# Sheet1.net
KiCad netlist of a schematic drawn in Altium Designer
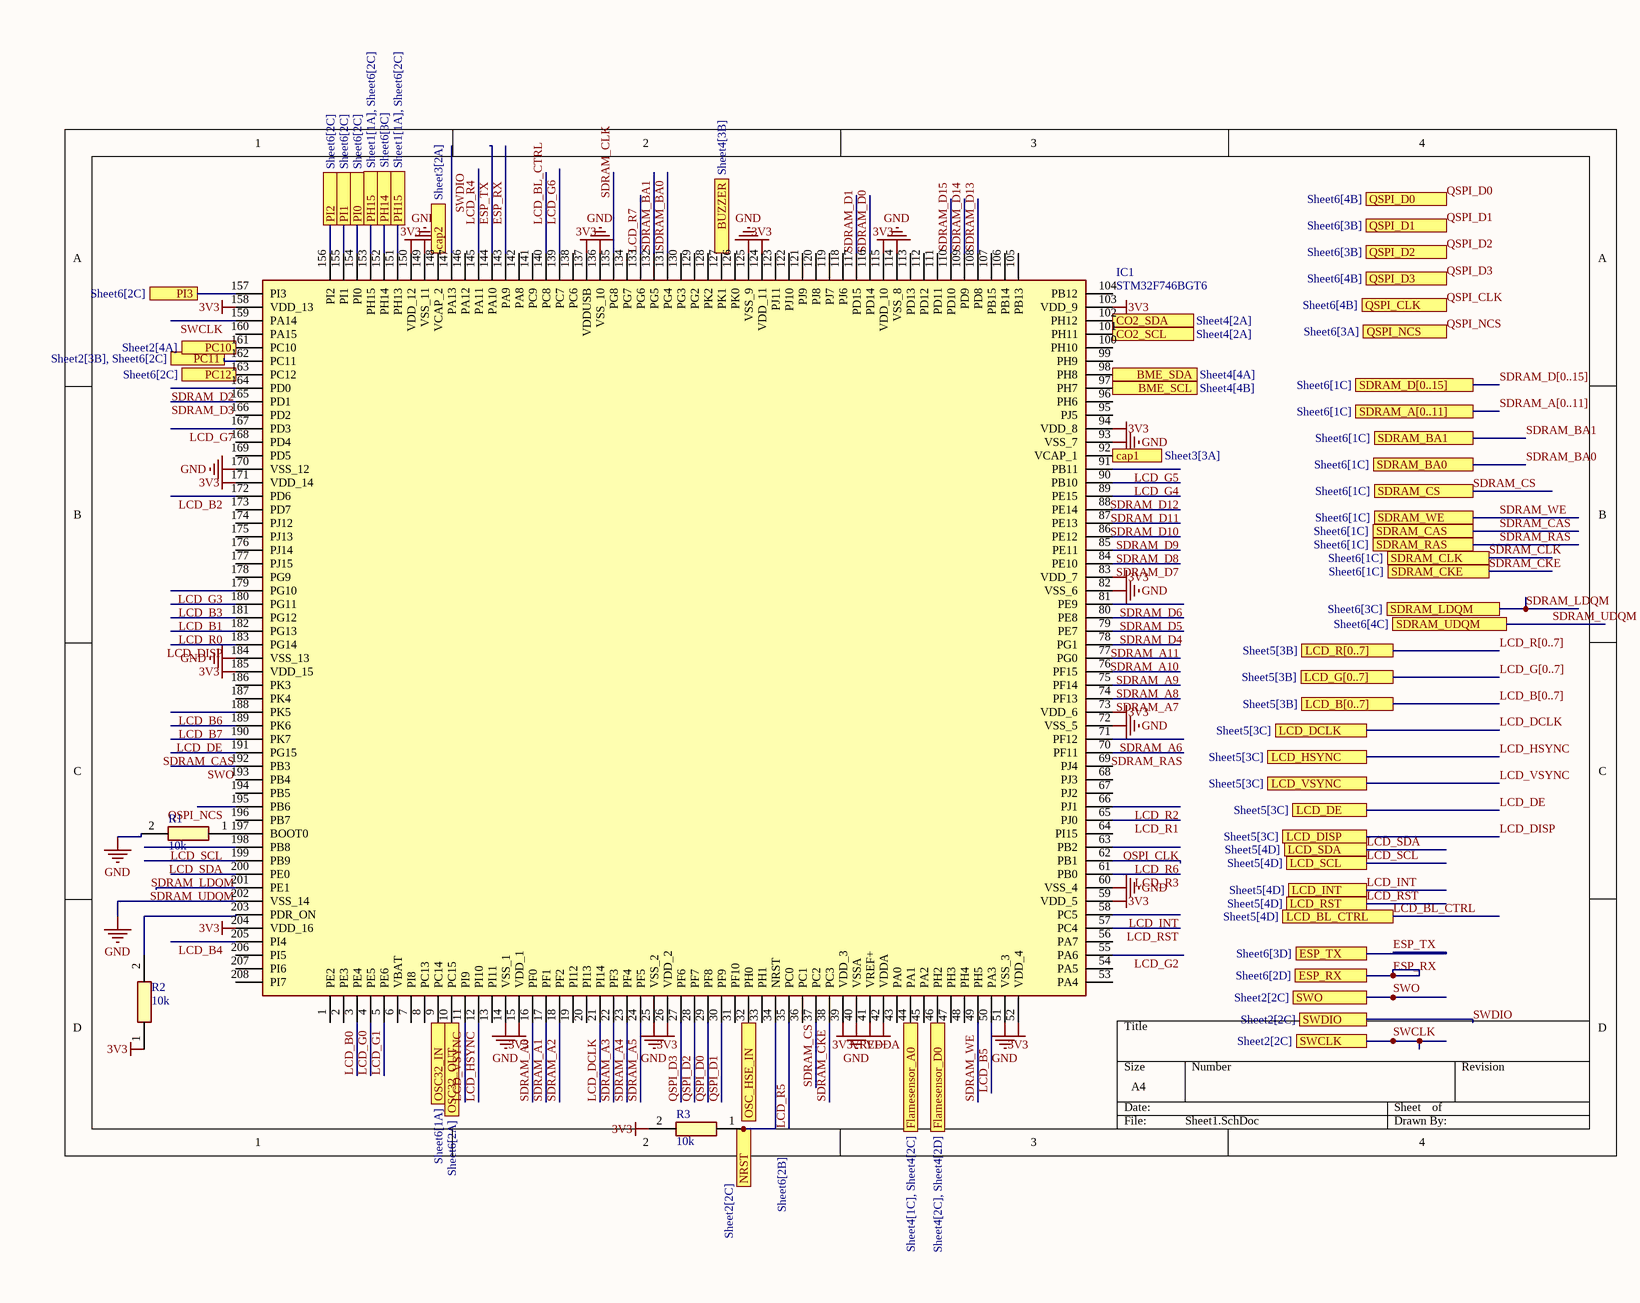
[diagram p0: Sheet1.SchDoc]

(export (version "E")
  (design (tool "Eeschema 10.0.6"))
  (components
    (comp (ref "IC1")
      (value "STM32F746BGT6")
      (footprint "SamacSys:QFP50P3000X3000X160-208N")
      (description "Integrated Circuit")
      (fields (field (name "MOUSER PART NUMBER") "511-STM32F746BGT6"))
      (libsource (lib "SamacSys") (part "STM32F746BGT6"))
    )
    (comp (ref "R1")
      (value "10k")
      (footprint "SamacSys:RESC1608X55N")
      (description "Resistor")
      (fields
        (field (name "MANUFACTURER_PART_NUMBER") "RC0603FR-071KL")
        (field (name "MOUSER PART NUMBER") "603-RC0603FR-071KL")
      )
      (libsource (lib "*") (part "RC0603FR-071KL"))
    )
    (comp (ref "R2")
      (value "10k")
      (footprint "SamacSys:RESC1608X55N")
      (description "Resistor")
      (fields
        (field (name "MANUFACTURER_PART_NUMBER") "RC0603FR-071KL")
        (field (name "MOUSER PART NUMBER") "603-RC0603FR-071KL")
      )
      (libsource (lib "") (part "RC0603FR-071KL_1"))
    )
    (comp (ref "R3")
      (value "10k")
      (footprint "SamacSys:RESC1608X55N")
      (description "Resistor")
      (fields
        (field (name "MANUFACTURER_PART_NUMBER") "RC0603FR-071KL")
        (field (name "MOUSER PART NUMBER") "603-RC0603FR-071KL")
      )
      (libsource (lib "*") (part "RC0603FR-071KL"))
    )
  )
  (nets
    (net (code "1") (name "/BME_SCL") (class "Default")
      (node (ref "IC1") (pin "97") (pinfunction "PH7_97") (pintype "passive"))
    )
    (net (code "2") (name "/BME_SDA") (class "Default")
      (node (ref "IC1") (pin "98") (pinfunction "PH8_98") (pintype "passive"))
    )
    (net (code "3") (name "/BUZZER") (class "Default")
      (node (ref "IC1") (pin "127") (pinfunction "PK1_127") (pintype "passive"))
    )
    (net (code "4") (name "/CO2_SCL") (class "Default")
      (node (ref "IC1") (pin "101") (pinfunction "PH11_101") (pintype "passive"))
    )
    (net (code "5") (name "/CO2_SDA") (class "Default")
      (node (ref "IC1") (pin "102") (pinfunction "PH12_102") (pintype "passive"))
    )
    (net (code "6") (name "/ESP_RX") (class "Default")
      (node (ref "IC1") (pin "143") (pinfunction "PA9_143") (pintype "passive"))
    )
    (net (code "7") (name "/ESP_TX") (class "Default")
      (node (ref "IC1") (pin "144") (pinfunction "PA10_144") (pintype "passive"))
    )
    (net (code "8") (name "/Flamesensor_A0") (class "Default")
      (node (ref "IC1") (pin "44") (pinfunction "PA1_44") (pintype "passive"))
    )
    (net (code "9") (name "/Flamesensor_D0") (class "Default")
      (node (ref "IC1") (pin "46") (pinfunction "PH2_46") (pintype "passive"))
    )
    (net (code "10") (name "/LCD_B0") (class "Default")
      (node (ref "IC1") (pin "3") (pinfunction "PE4_3") (pintype "passive"))
    )
    (net (code "11") (name "/LCD_B1") (class "Default")
      (node (ref "IC1") (pin "181") (pinfunction "PG12_181") (pintype "passive"))
    )
    (net (code "12") (name "/LCD_B2") (class "Default")
      (node (ref "IC1") (pin "172") (pinfunction "PD6_172") (pintype "passive"))
    )
    (net (code "13") (name "/LCD_B3") (class "Default")
      (node (ref "IC1") (pin "180") (pinfunction "PG11_180") (pintype "passive"))
    )
    (net (code "14") (name "/LCD_B4") (class "Default")
      (node (ref "IC1") (pin "205") (pinfunction "PI4_205") (pintype "passive"))
    )
    (net (code "15") (name "/LCD_B5") (class "Default")
      (node (ref "IC1") (pin "50") (pinfunction "PA3_50") (pintype "passive"))
    )
    (net (code "16") (name "/LCD_B6") (class "Default")
      (node (ref "IC1") (pin "188") (pinfunction "PK5_188") (pintype "passive"))
    )
    (net (code "17") (name "/LCD_B7") (class "Default")
      (node (ref "IC1") (pin "189") (pinfunction "PK6_189") (pintype "passive"))
    )
    (net (code "18") (name "/LCD_BL_CTRL") (class "Default")
      (node (ref "IC1") (pin "140") (pinfunction "PC8_140") (pintype "passive"))
    )
    (net (code "20") (name "/LCD_DCLK") (class "Default")
      (node (ref "IC1") (pin "21") (pinfunction "PI14_21") (pintype "passive"))
    )
    (net (code "21") (name "/LCD_DE") (class "Default")
      (node (ref "IC1") (pin "190") (pinfunction "PK7_190") (pintype "passive"))
    )
    (net (code "22") (name "/LCD_DISP") (class "Default")
      (node (ref "IC1") (pin "183") (pinfunction "PG14_183") (pintype "passive"))
    )
    (net (code "23") (name "/LCD_G0") (class "Default")
      (node (ref "IC1") (pin "4") (pinfunction "PE5_4") (pintype "passive"))
    )
    (net (code "24") (name "/LCD_G1") (class "Default")
      (node (ref "IC1") (pin "5") (pinfunction "PE6_5") (pintype "passive"))
    )
    (net (code "25") (name "/LCD_G2") (class "Default")
      (node (ref "IC1") (pin "55") (pinfunction "PA6_55") (pintype "passive"))
    )
    (net (code "26") (name "/LCD_G3") (class "Default")
      (node (ref "IC1") (pin "179") (pinfunction "PG10_179") (pintype "passive"))
    )
    (net (code "27") (name "/LCD_G4") (class "Default")
      (node (ref "IC1") (pin "90") (pinfunction "PB10_90") (pintype "passive"))
    )
    (net (code "28") (name "/LCD_G5") (class "Default")
      (node (ref "IC1") (pin "91") (pinfunction "PB11_91") (pintype "passive"))
    )
    (net (code "29") (name "/LCD_G6") (class "Default")
      (node (ref "IC1") (pin "139") (pinfunction "PC7_139") (pintype "passive"))
    )
    (net (code "30") (name "/LCD_G7") (class "Default")
      (node (ref "IC1") (pin "167") (pinfunction "PD3_167") (pintype "passive"))
    )
    (net (code "32") (name "/LCD_HSYNC") (class "Default")
      (node (ref "IC1") (pin "12") (pinfunction "PI10_12") (pintype "passive"))
    )
    (net (code "33") (name "/LCD_INT") (class "Default")
      (node (ref "IC1") (pin "58") (pinfunction "PC5_58") (pintype "passive"))
    )
    (net (code "34") (name "/LCD_R0") (class "Default")
      (node (ref "IC1") (pin "182") (pinfunction "PG13_182") (pintype "passive"))
    )
    (net (code "35") (name "/LCD_R1") (class "Default")
      (node (ref "IC1") (pin "65") (pinfunction "PJ0_65") (pintype "passive"))
    )
    (net (code "36") (name "/LCD_R2") (class "Default")
      (node (ref "IC1") (pin "66") (pinfunction "PJ1_66") (pintype "passive"))
    )
    (net (code "37") (name "/LCD_R3") (class "Default")
      (node (ref "IC1") (pin "61") (pinfunction "PB0_61") (pintype "passive"))
    )
    (net (code "38") (name "/LCD_R4") (class "Default")
      (node (ref "IC1") (pin "145") (pinfunction "PA11_145") (pintype "passive"))
    )
    (net (code "39") (name "/LCD_R5") (class "Default")
      (node (ref "IC1") (pin "35") (pinfunction "PC0_35") (pintype "passive"))
    )
    (net (code "40") (name "/LCD_R6") (class "Default")
      (node (ref "IC1") (pin "62") (pinfunction "PB1_62") (pintype "passive"))
    )
    (net (code "41") (name "/LCD_R7") (class "Default")
      (node (ref "IC1") (pin "133") (pinfunction "PG6_133") (pintype "passive"))
    )
    (net (code "42") (name "/LCD_RST") (class "Default")
      (node (ref "IC1") (pin "57") (pinfunction "PC4_57") (pintype "passive"))
    )
    (net (code "44") (name "/LCD_SCL") (class "Default")
      (node (ref "IC1") (pin "198") (pinfunction "PB8_198") (pintype "passive"))
    )
    (net (code "45") (name "/LCD_SDA") (class "Default")
      (node (ref "IC1") (pin "199") (pinfunction "PB9_199") (pintype "passive"))
    )
    (net (code "46") (name "/LCD_VSYNC") (class "Default")
      (node (ref "IC1") (pin "11") (pinfunction "PI9_11") (pintype "passive"))
    )
    (net (code "47") (name "/NRST") (class "Default")
      (node (ref "IC1") (pin "34") (pinfunction "NRST_34") (pintype "passive"))
      (node (ref "R3") (pin "1") (pinfunction "1_1") (pintype "passive"))
    )
    (net (code "48") (name "/OSC32_IN") (class "Default")
      (node (ref "IC1") (pin "9") (pinfunction "PC14_9") (pintype "passive"))
    )
    (net (code "49") (name "/OSC32_OUT") (class "Default")
      (node (ref "IC1") (pin "10") (pinfunction "PC15_10") (pintype "passive"))
    )
    (net (code "50") (name "/OSC_HSE_IN") (class "Default")
      (node (ref "IC1") (pin "32") (pinfunction "PH0_32") (pintype "passive"))
    )
    (net (code "51") (name "/PC10") (class "Default")
      (node (ref "IC1") (pin "161") (pinfunction "PC10_161") (pintype "passive"))
    )
    (net (code "52") (name "/PC11") (class "Default")
      (node (ref "IC1") (pin "162") (pinfunction "PC11_162") (pintype "passive"))
    )
    (net (code "53") (name "/PC12") (class "Default")
      (node (ref "IC1") (pin "163") (pinfunction "PC12_163") (pintype "passive"))
    )
    (net (code "54") (name "/PH14") (class "Default")
      (node (ref "IC1") (pin "152") (pinfunction "PH14_152") (pintype "passive"))
    )
    (net (code "55") (name "/PH15") (class "Default")
      (node (ref "IC1") (pin "151") (pinfunction "PH13_151") (pintype "passive"))
      (node (ref "IC1") (pin "153") (pinfunction "PH15_153") (pintype "passive"))
    )
    (net (code "56") (name "/PI0") (class "Default")
      (node (ref "IC1") (pin "154") (pinfunction "PI0_154") (pintype "passive"))
    )
    (net (code "57") (name "/PI1") (class "Default")
      (node (ref "IC1") (pin "155") (pinfunction "PI1_155") (pintype "passive"))
    )
    (net (code "58") (name "/PI2") (class "Default")
      (node (ref "IC1") (pin "156") (pinfunction "PI2_156") (pintype "passive"))
    )
    (net (code "59") (name "/PI3") (class "Default")
      (node (ref "IC1") (pin "157") (pinfunction "PI3_157") (pintype "passive"))
    )
    (net (code "60") (name "/QSPI_CLK") (class "Default")
      (node (ref "IC1") (pin "63") (pinfunction "PB2_63") (pintype "passive"))
    )
    (net (code "61") (name "/QSPI_D0") (class "Default")
      (node (ref "IC1") (pin "29") (pinfunction "PF8_29") (pintype "passive"))
    )
    (net (code "62") (name "/QSPI_D1") (class "Default")
      (node (ref "IC1") (pin "30") (pinfunction "PF9_30") (pintype "passive"))
    )
    (net (code "63") (name "/QSPI_D2") (class "Default")
      (node (ref "IC1") (pin "28") (pinfunction "PF7_28") (pintype "passive"))
    )
    (net (code "64") (name "/QSPI_D3") (class "Default")
      (node (ref "IC1") (pin "27") (pinfunction "PF6_27") (pintype "passive"))
    )
    (net (code "65") (name "/QSPI_NCS") (class "Default")
      (node (ref "IC1") (pin "195") (pinfunction "PB6_195") (pintype "passive"))
    )
    (net (code "66") (name "/SDRAM_A0") (class "Default")
      (node (ref "IC1") (pin "16") (pinfunction "PF0_16") (pintype "passive"))
    )
    (net (code "67") (name "/SDRAM_A1") (class "Default")
      (node (ref "IC1") (pin "17") (pinfunction "PF1_17") (pintype "passive"))
    )
    (net (code "68") (name "/SDRAM_A2") (class "Default")
      (node (ref "IC1") (pin "18") (pinfunction "PF2_18") (pintype "passive"))
    )
    (net (code "69") (name "/SDRAM_A3") (class "Default")
      (node (ref "IC1") (pin "22") (pinfunction "PF3_22") (pintype "passive"))
    )
    (net (code "70") (name "/SDRAM_A4") (class "Default")
      (node (ref "IC1") (pin "23") (pinfunction "PF4_23") (pintype "passive"))
    )
    (net (code "71") (name "/SDRAM_A5") (class "Default")
      (node (ref "IC1") (pin "24") (pinfunction "PF5_24") (pintype "passive"))
    )
    (net (code "72") (name "/SDRAM_A6") (class "Default")
      (node (ref "IC1") (pin "71") (pinfunction "PF12_71") (pintype "passive"))
    )
    (net (code "73") (name "/SDRAM_A7") (class "Default")
      (node (ref "IC1") (pin "74") (pinfunction "PF13_74") (pintype "passive"))
    )
    (net (code "74") (name "/SDRAM_A8") (class "Default")
      (node (ref "IC1") (pin "75") (pinfunction "PF14_75") (pintype "passive"))
    )
    (net (code "75") (name "/SDRAM_A9") (class "Default")
      (node (ref "IC1") (pin "76") (pinfunction "PF15_76") (pintype "passive"))
    )
    (net (code "76") (name "/SDRAM_A10") (class "Default")
      (node (ref "IC1") (pin "77") (pinfunction "PG0_77") (pintype "passive"))
    )
    (net (code "77") (name "/SDRAM_A11") (class "Default")
      (node (ref "IC1") (pin "78") (pinfunction "PG1_78") (pintype "passive"))
    )
    (net (code "79") (name "/SDRAM_BA0") (class "Default")
      (node (ref "IC1") (pin "131") (pinfunction "PG4_131") (pintype "passive"))
    )
    (net (code "80") (name "/SDRAM_BA1") (class "Default")
      (node (ref "IC1") (pin "132") (pinfunction "PG5_132") (pintype "passive"))
    )
    (net (code "81") (name "/SDRAM_CAS") (class "Default")
      (node (ref "IC1") (pin "191") (pinfunction "PG15_191") (pintype "passive"))
    )
    (net (code "82") (name "/SDRAM_CKE") (class "Default")
      (node (ref "IC1") (pin "38") (pinfunction "PC3_38") (pintype "passive"))
    )
    (net (code "83") (name "/SDRAM_CLK") (class "Default")
      (node (ref "IC1") (pin "135") (pinfunction "PG8_135") (pintype "passive"))
    )
    (net (code "84") (name "/SDRAM_CS") (class "Default")
      (node (ref "IC1") (pin "37") (pinfunction "PC2_37") (pintype "passive"))
    )
    (net (code "85") (name "/SDRAM_D0") (class "Default")
      (node (ref "IC1") (pin "116") (pinfunction "PD14_116") (pintype "passive"))
    )
    (net (code "86") (name "/SDRAM_D1") (class "Default")
      (node (ref "IC1") (pin "117") (pinfunction "PD15_117") (pintype "passive"))
    )
    (net (code "87") (name "/SDRAM_D2") (class "Default")
      (node (ref "IC1") (pin "164") (pinfunction "PD0_164") (pintype "passive"))
    )
    (net (code "88") (name "/SDRAM_D3") (class "Default")
      (node (ref "IC1") (pin "165") (pinfunction "PD1_165") (pintype "passive"))
    )
    (net (code "89") (name "/SDRAM_D4") (class "Default")
      (node (ref "IC1") (pin "79") (pinfunction "PE7_79") (pintype "passive"))
    )
    (net (code "90") (name "/SDRAM_D5") (class "Default")
      (node (ref "IC1") (pin "80") (pinfunction "PE8_80") (pintype "passive"))
    )
    (net (code "91") (name "/SDRAM_D6") (class "Default")
      (node (ref "IC1") (pin "81") (pinfunction "PE9_81") (pintype "passive"))
    )
    (net (code "92") (name "/SDRAM_D7") (class "Default")
      (node (ref "IC1") (pin "84") (pinfunction "PE10_84") (pintype "passive"))
    )
    (net (code "93") (name "/SDRAM_D8") (class "Default")
      (node (ref "IC1") (pin "85") (pinfunction "PE11_85") (pintype "passive"))
    )
    (net (code "94") (name "/SDRAM_D9") (class "Default")
      (node (ref "IC1") (pin "86") (pinfunction "PE12_86") (pintype "passive"))
    )
    (net (code "95") (name "/SDRAM_D10") (class "Default")
      (node (ref "IC1") (pin "87") (pinfunction "PE13_87") (pintype "passive"))
    )
    (net (code "96") (name "/SDRAM_D11") (class "Default")
      (node (ref "IC1") (pin "88") (pinfunction "PE14_88") (pintype "passive"))
    )
    (net (code "97") (name "/SDRAM_D12") (class "Default")
      (node (ref "IC1") (pin "89") (pinfunction "PE15_89") (pintype "passive"))
    )
    (net (code "98") (name "/SDRAM_D13") (class "Default")
      (node (ref "IC1") (pin "108") (pinfunction "PD8_108") (pintype "passive"))
    )
    (net (code "99") (name "/SDRAM_D14") (class "Default")
      (node (ref "IC1") (pin "109") (pinfunction "PD9_109") (pintype "passive"))
    )
    (net (code "100") (name "/SDRAM_D15") (class "Default")
      (node (ref "IC1") (pin "110") (pinfunction "PD10_110") (pintype "passive"))
    )
    (net (code "102") (name "/SDRAM_LDQM") (class "Default")
      (node (ref "IC1") (pin "200") (pinfunction "PE0_200") (pintype "passive"))
    )
    (net (code "103") (name "/SDRAM_RAS") (class "Default")
      (node (ref "IC1") (pin "70") (pinfunction "PF11_70") (pintype "passive"))
    )
    (net (code "104") (name "/SDRAM_UDQM") (class "Default")
      (node (ref "IC1") (pin "201") (pinfunction "PE1_201") (pintype "passive"))
    )
    (net (code "105") (name "/SDRAM_WE") (class "Default")
      (node (ref "IC1") (pin "49") (pinfunction "PH5_49") (pintype "passive"))
    )
    (net (code "106") (name "/SWCLK") (class "Default")
      (node (ref "IC1") (pin "159") (pinfunction "PA14_159") (pintype "passive"))
    )
    (net (code "107") (name "/SWDIO") (class "Default")
      (node (ref "IC1") (pin "147") (pinfunction "PA13_147") (pintype "passive"))
    )
    (net (code "108") (name "/SWO") (class "Default")
      (node (ref "IC1") (pin "192") (pinfunction "PB3_192") (pintype "passive"))
    )
    (net (code "109") (name "/cap1") (class "Default")
      (node (ref "IC1") (pin "92") (pinfunction "VCAP_1_92") (pintype "passive"))
    )
    (net (code "110") (name "/cap2") (class "Default")
      (node (ref "IC1") (pin "148") (pinfunction "VCAP_2_148") (pintype "passive"))
    )
    (net (code "111") (name "3V3") (class "Default")
      (node (ref "IC1") (pin "103") (pinfunction "VDD_9_103") (pintype "passive"))
      (node (ref "IC1") (pin "115") (pinfunction "VDD_10_115") (pintype "passive"))
      (node (ref "IC1") (pin "124") (pinfunction "VDD_11_124") (pintype "passive"))
      (node (ref "IC1") (pin "137") (pinfunction "VDDUSB_137") (pintype "passive"))
      (node (ref "IC1") (pin "15") (pinfunction "VDD_1_15") (pintype "passive"))
      (node (ref "IC1") (pin "150") (pinfunction "VDD_12_150") (pintype "passive"))
      (node (ref "IC1") (pin "158") (pinfunction "VDD_13_158") (pintype "passive"))
      (node (ref "IC1") (pin "171") (pinfunction "VDD_14_171") (pintype "passive"))
      (node (ref "IC1") (pin "185") (pinfunction "VDD_15_185") (pintype "passive"))
      (node (ref "IC1") (pin "204") (pinfunction "VDD_16_204") (pintype "passive"))
      (node (ref "IC1") (pin "26") (pinfunction "VDD_2_26") (pintype "passive"))
      (node (ref "IC1") (pin "39") (pinfunction "VDD_3_39") (pintype "passive"))
      (node (ref "IC1") (pin "52") (pinfunction "VDD_4_52") (pintype "passive"))
      (node (ref "IC1") (pin "59") (pinfunction "VDD_5_59") (pintype "passive"))
      (node (ref "IC1") (pin "73") (pinfunction "VDD_6_73") (pintype "passive"))
      (node (ref "IC1") (pin "83") (pinfunction "VDD_7_83") (pintype "passive"))
      (node (ref "IC1") (pin "94") (pinfunction "VDD_8_94") (pintype "passive"))
      (node (ref "R2") (pin "1") (pinfunction "1_1") (pintype "passive"))
      (node (ref "R3") (pin "2") (pinfunction "2_2") (pintype "passive"))
    )
    (net (code "112") (name "GND") (class "Default")
      (node (ref "IC1") (pin "114") (pinfunction "VSS_8_114") (pintype "passive"))
      (node (ref "IC1") (pin "125") (pinfunction "VSS_9_125") (pintype "passive"))
      (node (ref "IC1") (pin "136") (pinfunction "VSS_10_136") (pintype "passive"))
      (node (ref "IC1") (pin "14") (pinfunction "VSS_1_14") (pintype "passive"))
      (node (ref "IC1") (pin "149") (pinfunction "VSS_11_149") (pintype "passive"))
      (node (ref "IC1") (pin "170") (pinfunction "VSS_12_170") (pintype "passive"))
      (node (ref "IC1") (pin "184") (pinfunction "VSS_13_184") (pintype "passive"))
      (node (ref "IC1") (pin "202") (pinfunction "VSS_14_202") (pintype "passive"))
      (node (ref "IC1") (pin "25") (pinfunction "VSS_2_25") (pintype "passive"))
      (node (ref "IC1") (pin "40") (pinfunction "VSSA_40") (pintype "passive"))
      (node (ref "IC1") (pin "51") (pinfunction "VSS_3_51") (pintype "passive"))
      (node (ref "IC1") (pin "60") (pinfunction "VSS_4_60") (pintype "passive"))
      (node (ref "IC1") (pin "72") (pinfunction "VSS_5_72") (pintype "passive"))
      (node (ref "IC1") (pin "82") (pinfunction "VSS_6_82") (pintype "passive"))
      (node (ref "IC1") (pin "93") (pinfunction "VSS_7_93") (pintype "passive"))
      (node (ref "R1") (pin "2") (pinfunction "2_2") (pintype "passive"))
    )
    (net (code "113") (name "Net-(IC1-BOOT0)") (class "Default")
      (node (ref "IC1") (pin "197") (pinfunction "BOOT0_197") (pintype "passive"))
      (node (ref "R1") (pin "1") (pinfunction "1_1") (pintype "passive"))
    )
    (net (code "114") (name "Net-(IC1-PDR_ON)") (class "Default")
      (node (ref "IC1") (pin "203") (pinfunction "PDR_ON_203") (pintype "passive"))
      (node (ref "R2") (pin "2") (pinfunction "2_2") (pintype "passive"))
    )
    (net (code "115") (name "VDDA") (class "Default")
      (node (ref "IC1") (pin "42") (pinfunction "VDDA_42") (pintype "passive"))
    )
    (net (code "116") (name "VREF+") (class "Default")
      (node (ref "IC1") (pin "41") (pinfunction "VREF+_41") (pintype "passive"))
    )
    (net (code "117") (name "unconnected-(IC1-PA0-Pad43)") (class "Default")
      (node (ref "IC1") (pin "43") (pinfunction "PA0_43") (pintype "passive"))
    )
    (net (code "118") (name "unconnected-(IC1-PA2-Pad45)") (class "Default")
      (node (ref "IC1") (pin "45") (pinfunction "PA2_45") (pintype "passive"))
    )
    (net (code "119") (name "unconnected-(IC1-PA4-Pad53)") (class "Default")
      (node (ref "IC1") (pin "53") (pinfunction "PA4_53") (pintype "passive"))
    )
    (net (code "120") (name "unconnected-(IC1-PA5-Pad54)") (class "Default")
      (node (ref "IC1") (pin "54") (pinfunction "PA5_54") (pintype "passive"))
    )
    (net (code "121") (name "unconnected-(IC1-PA7-Pad56)") (class "Default")
      (node (ref "IC1") (pin "56") (pinfunction "PA7_56") (pintype "passive"))
    )
    (net (code "122") (name "unconnected-(IC1-PA8-Pad142)") (class "Default")
      (node (ref "IC1") (pin "142") (pinfunction "PA8_142") (pintype "passive"))
    )
    (net (code "123") (name "unconnected-(IC1-PA12-Pad146)") (class "Default")
      (node (ref "IC1") (pin "146") (pinfunction "PA12_146") (pintype "passive"))
    )
    (net (code "124") (name "unconnected-(IC1-PA15-Pad160)") (class "Default")
      (node (ref "IC1") (pin "160") (pinfunction "PA15_160") (pintype "passive"))
    )
    (net (code "125") (name "unconnected-(IC1-PB4-Pad193)") (class "Default")
      (node (ref "IC1") (pin "193") (pinfunction "PB4_193") (pintype "passive"))
    )
    (net (code "126") (name "unconnected-(IC1-PB5-Pad194)") (class "Default")
      (node (ref "IC1") (pin "194") (pinfunction "PB5_194") (pintype "passive"))
    )
    (net (code "127") (name "unconnected-(IC1-PB7-Pad196)") (class "Default")
      (node (ref "IC1") (pin "196") (pinfunction "PB7_196") (pintype "passive"))
    )
    (net (code "128") (name "unconnected-(IC1-PB12-Pad104)") (class "Default")
      (node (ref "IC1") (pin "104") (pinfunction "PB12_104") (pintype "passive"))
    )
    (net (code "129") (name "unconnected-(IC1-PB13-Pad105)") (class "Default")
      (node (ref "IC1") (pin "105") (pinfunction "PB13_105") (pintype "passive"))
    )
    (net (code "130") (name "unconnected-(IC1-PB14-Pad106)") (class "Default")
      (node (ref "IC1") (pin "106") (pinfunction "PB14_106") (pintype "passive"))
    )
    (net (code "131") (name "unconnected-(IC1-PB15-Pad107)") (class "Default")
      (node (ref "IC1") (pin "107") (pinfunction "PB15_107") (pintype "passive"))
    )
    (net (code "132") (name "unconnected-(IC1-PC1-Pad36)") (class "Default")
      (node (ref "IC1") (pin "36") (pinfunction "PC1_36") (pintype "passive"))
    )
    (net (code "133") (name "unconnected-(IC1-PC6-Pad138)") (class "Default")
      (node (ref "IC1") (pin "138") (pinfunction "PC6_138") (pintype "passive"))
    )
    (net (code "134") (name "unconnected-(IC1-PC9-Pad141)") (class "Default")
      (node (ref "IC1") (pin "141") (pinfunction "PC9_141") (pintype "passive"))
    )
    (net (code "135") (name "unconnected-(IC1-PC13-Pad8)") (class "Default")
      (node (ref "IC1") (pin "8") (pinfunction "PC13_8") (pintype "passive"))
    )
    (net (code "136") (name "unconnected-(IC1-PD2-Pad166)") (class "Default")
      (node (ref "IC1") (pin "166") (pinfunction "PD2_166") (pintype "passive"))
    )
    (net (code "137") (name "unconnected-(IC1-PD4-Pad168)") (class "Default")
      (node (ref "IC1") (pin "168") (pinfunction "PD4_168") (pintype "passive"))
    )
    (net (code "138") (name "unconnected-(IC1-PD5-Pad169)") (class "Default")
      (node (ref "IC1") (pin "169") (pinfunction "PD5_169") (pintype "passive"))
    )
    (net (code "139") (name "unconnected-(IC1-PD7-Pad173)") (class "Default")
      (node (ref "IC1") (pin "173") (pinfunction "PD7_173") (pintype "passive"))
    )
    (net (code "140") (name "unconnected-(IC1-PD11-Pad111)") (class "Default")
      (node (ref "IC1") (pin "111") (pinfunction "PD11_111") (pintype "passive"))
    )
    (net (code "141") (name "unconnected-(IC1-PD12-Pad112)") (class "Default")
      (node (ref "IC1") (pin "112") (pinfunction "PD12_112") (pintype "passive"))
    )
    (net (code "142") (name "unconnected-(IC1-PD13-Pad113)") (class "Default")
      (node (ref "IC1") (pin "113") (pinfunction "PD13_113") (pintype "passive"))
    )
    (net (code "143") (name "unconnected-(IC1-PE2-Pad1)") (class "Default")
      (node (ref "IC1") (pin "1") (pinfunction "PE2_1") (pintype "passive"))
    )
    (net (code "144") (name "unconnected-(IC1-PE3-Pad2)") (class "Default")
      (node (ref "IC1") (pin "2") (pinfunction "PE3_2") (pintype "passive"))
    )
    (net (code "145") (name "unconnected-(IC1-PF10-Pad31)") (class "Default")
      (node (ref "IC1") (pin "31") (pinfunction "PF10_31") (pintype "passive"))
    )
    (net (code "146") (name "unconnected-(IC1-PG2-Pad129)") (class "Default")
      (node (ref "IC1") (pin "129") (pinfunction "PG2_129") (pintype "passive"))
    )
    (net (code "147") (name "unconnected-(IC1-PG3-Pad130)") (class "Default")
      (node (ref "IC1") (pin "130") (pinfunction "PG3_130") (pintype "passive"))
    )
    (net (code "148") (name "unconnected-(IC1-PG7-Pad134)") (class "Default")
      (node (ref "IC1") (pin "134") (pinfunction "PG7_134") (pintype "passive"))
    )
    (net (code "149") (name "unconnected-(IC1-PG9-Pad178)") (class "Default")
      (node (ref "IC1") (pin "178") (pinfunction "PG9_178") (pintype "passive"))
    )
    (net (code "150") (name "unconnected-(IC1-PH1-Pad33)") (class "Default")
      (node (ref "IC1") (pin "33") (pinfunction "PH1_33") (pintype "passive"))
    )
    (net (code "151") (name "unconnected-(IC1-PH3-Pad47)") (class "Default")
      (node (ref "IC1") (pin "47") (pinfunction "PH3_47") (pintype "passive"))
    )
    (net (code "152") (name "unconnected-(IC1-PH4-Pad48)") (class "Default")
      (node (ref "IC1") (pin "48") (pinfunction "PH4_48") (pintype "passive"))
    )
    (net (code "153") (name "unconnected-(IC1-PH6-Pad96)") (class "Default")
      (node (ref "IC1") (pin "96") (pinfunction "PH6_96") (pintype "passive"))
    )
    (net (code "154") (name "unconnected-(IC1-PH9-Pad99)") (class "Default")
      (node (ref "IC1") (pin "99") (pinfunction "PH9_99") (pintype "passive"))
    )
    (net (code "155") (name "unconnected-(IC1-PH10-Pad100)") (class "Default")
      (node (ref "IC1") (pin "100") (pinfunction "PH10_100") (pintype "passive"))
    )
    (net (code "156") (name "unconnected-(IC1-PI5-Pad206)") (class "Default")
      (node (ref "IC1") (pin "206") (pinfunction "PI5_206") (pintype "passive"))
    )
    (net (code "157") (name "unconnected-(IC1-PI6-Pad207)") (class "Default")
      (node (ref "IC1") (pin "207") (pinfunction "PI6_207") (pintype "passive"))
    )
    (net (code "158") (name "unconnected-(IC1-PI7-Pad208)") (class "Default")
      (node (ref "IC1") (pin "208") (pinfunction "PI7_208") (pintype "passive"))
    )
    (net (code "159") (name "unconnected-(IC1-PI8-Pad7)") (class "Default")
      (node (ref "IC1") (pin "7") (pinfunction "PI8_7") (pintype "passive"))
    )
    (net (code "160") (name "unconnected-(IC1-PI11-Pad13)") (class "Default")
      (node (ref "IC1") (pin "13") (pinfunction "PI11_13") (pintype "passive"))
    )
    (net (code "161") (name "unconnected-(IC1-PI12-Pad19)") (class "Default")
      (node (ref "IC1") (pin "19") (pinfunction "PI12_19") (pintype "passive"))
    )
    (net (code "162") (name "unconnected-(IC1-PI13-Pad20)") (class "Default")
      (node (ref "IC1") (pin "20") (pinfunction "PI13_20") (pintype "passive"))
    )
    (net (code "163") (name "unconnected-(IC1-PI15-Pad64)") (class "Default")
      (node (ref "IC1") (pin "64") (pinfunction "PI15_64") (pintype "passive"))
    )
    (net (code "164") (name "unconnected-(IC1-PJ2-Pad67)") (class "Default")
      (node (ref "IC1") (pin "67") (pinfunction "PJ2_67") (pintype "passive"))
    )
    (net (code "165") (name "unconnected-(IC1-PJ3-Pad68)") (class "Default")
      (node (ref "IC1") (pin "68") (pinfunction "PJ3_68") (pintype "passive"))
    )
    (net (code "166") (name "unconnected-(IC1-PJ4-Pad69)") (class "Default")
      (node (ref "IC1") (pin "69") (pinfunction "PJ4_69") (pintype "passive"))
    )
    (net (code "167") (name "unconnected-(IC1-PJ5-Pad95)") (class "Default")
      (node (ref "IC1") (pin "95") (pinfunction "PJ5_95") (pintype "passive"))
    )
    (net (code "168") (name "unconnected-(IC1-PJ6-Pad118)") (class "Default")
      (node (ref "IC1") (pin "118") (pinfunction "PJ6_118") (pintype "passive"))
    )
    (net (code "169") (name "unconnected-(IC1-PJ7-Pad119)") (class "Default")
      (node (ref "IC1") (pin "119") (pinfunction "PJ7_119") (pintype "passive"))
    )
    (net (code "170") (name "unconnected-(IC1-PJ8-Pad120)") (class "Default")
      (node (ref "IC1") (pin "120") (pinfunction "PJ8_120") (pintype "passive"))
    )
    (net (code "171") (name "unconnected-(IC1-PJ9-Pad121)") (class "Default")
      (node (ref "IC1") (pin "121") (pinfunction "PJ9_121") (pintype "passive"))
    )
    (net (code "172") (name "unconnected-(IC1-PJ10-Pad122)") (class "Default")
      (node (ref "IC1") (pin "122") (pinfunction "PJ10_122") (pintype "passive"))
    )
    (net (code "173") (name "unconnected-(IC1-PJ11-Pad123)") (class "Default")
      (node (ref "IC1") (pin "123") (pinfunction "PJ11_123") (pintype "passive"))
    )
    (net (code "174") (name "unconnected-(IC1-PJ12-Pad174)") (class "Default")
      (node (ref "IC1") (pin "174") (pinfunction "PJ12_174") (pintype "passive"))
    )
    (net (code "175") (name "unconnected-(IC1-PJ13-Pad175)") (class "Default")
      (node (ref "IC1") (pin "175") (pinfunction "PJ13_175") (pintype "passive"))
    )
    (net (code "176") (name "unconnected-(IC1-PJ14-Pad176)") (class "Default")
      (node (ref "IC1") (pin "176") (pinfunction "PJ14_176") (pintype "passive"))
    )
    (net (code "177") (name "unconnected-(IC1-PJ15-Pad177)") (class "Default")
      (node (ref "IC1") (pin "177") (pinfunction "PJ15_177") (pintype "passive"))
    )
    (net (code "178") (name "unconnected-(IC1-PK0-Pad126)") (class "Default")
      (node (ref "IC1") (pin "126") (pinfunction "PK0_126") (pintype "passive"))
    )
    (net (code "179") (name "unconnected-(IC1-PK2-Pad128)") (class "Default")
      (node (ref "IC1") (pin "128") (pinfunction "PK2_128") (pintype "passive"))
    )
    (net (code "180") (name "unconnected-(IC1-PK3-Pad186)") (class "Default")
      (node (ref "IC1") (pin "186") (pinfunction "PK3_186") (pintype "passive"))
    )
    (net (code "181") (name "unconnected-(IC1-PK4-Pad187)") (class "Default")
      (node (ref "IC1") (pin "187") (pinfunction "PK4_187") (pintype "passive"))
    )
    (net (code "182") (name "unconnected-(IC1-VBAT-Pad6)") (class "Default")
      (node (ref "IC1") (pin "6") (pinfunction "VBAT_6") (pintype "passive"))
    )
  )
)
